# isolated_rs485.net
KiCad netlist of a schematic drawn in Altium Designer
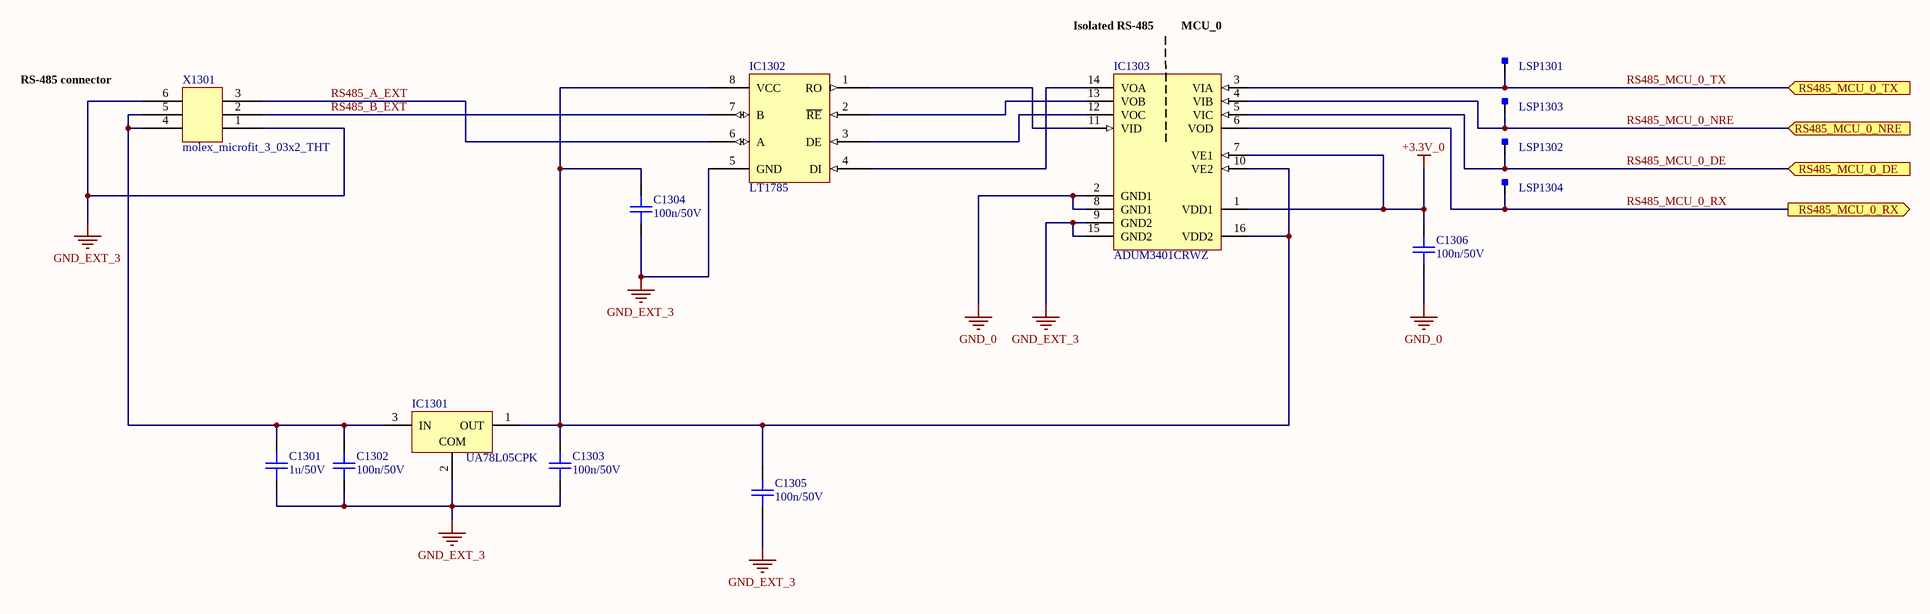
[diagram p0: isolated_rs485.SchDoc]

(export (version "E")
  (design (tool "Eeschema 10.0.6"))
  (components
    (comp (ref "C1301")
      (value "1u/50V")
      (footprint "CAPC1608X08N")
      (description "MLCC")
      (fields (field (name "PART NUMBER") "gen_C_ceramic_1u_50V_X7R_0603") (field (name "TOLERANCE") "± 10%"))
      (libsource (lib "OE750") (part "C"))
    )
    (comp (ref "C1302")
      (value "100n/50V")
      (footprint "CAPC1608X08N")
      (description "MLCC")
      (fields (field (name "PART NUMBER") "gen_C_ceramic_100n_50V_X7R_0603"))
      (libsource (lib "OE750") (part "C"))
    )
    (comp (ref "C1303")
      (value "100n/50V")
      (footprint "CAPC1608X08N")
      (description "MLCC")
      (fields (field (name "PART NUMBER") "gen_C_ceramic_100n_50V_X7R_0603"))
      (libsource (lib "OE750") (part "C"))
    )
    (comp (ref "C1304")
      (value "100n/50V")
      (footprint "CAPC1608X08N")
      (description "MLCC")
      (fields (field (name "PART NUMBER") "gen_C_ceramic_100n_50V_X7R_0603"))
      (libsource (lib "OE750") (part "C"))
    )
    (comp (ref "C1305")
      (value "100n/50V")
      (footprint "CAPC1608X08N")
      (description "MLCC")
      (fields (field (name "PART NUMBER") "gen_C_ceramic_100n_50V_X7R_0603"))
      (libsource (lib "OE750") (part "C"))
    )
    (comp (ref "C1306")
      (value "100n/50V")
      (footprint "CAPC1608X08N")
      (description "MLCC")
      (fields (field (name "PART NUMBER") "gen_C_ceramic_100n_50V_X7R_0603"))
      (libsource (lib "OE750") (part "C"))
    )
    (comp (ref "IC1301")
      (value "UA78L05CPK")
      (footprint "PK0003A_L")
      (fields (field (name "MANUFACTURER") "TexasInstruments"))
      (libsource (lib "Altium Content Vault") (part "TI-UA78L05-PK-3"))
    )
    (comp (ref "IC1302")
      (value "LT1785")
      (footprint "SOIC127P600X175-8N")
      (description "Transceiver RS422/RS485, Fault Protected, 4.75V-5.25V supply, SOIC-8")
      (fields (field (name "PART NUMBER") "LT1785CS8#PBF") (field (name "MANUFACTURER") "Linear Technology"))
      (libsource (lib "OE750") (part "LT1785"))
    )
    (comp (ref "IC1303")
      (value "ADUM3401CRWZ")
      (footprint "ADI-RW-16_N")
      (fields (field (name "MANUFACTURER") "Analog Devices"))
      (libsource (lib "Altium Content Vault") (part "ADI-ADUMX4X1-16"))
    )
    (comp (ref "LSP1301")
      (value "Testpoint_Square")
      (footprint "Testpoint_S1")
      (description "Testpoint, square")
      (libsource (lib "OE750") (part "Testpoint_Square"))
    )
    (comp (ref "LSP1302")
      (value "Testpoint_Square")
      (footprint "Testpoint_S1")
      (description "Testpoint, square")
      (libsource (lib "OE750") (part "Testpoint_Square"))
    )
    (comp (ref "LSP1303")
      (value "Testpoint_Square")
      (footprint "Testpoint_S1")
      (description "Testpoint, square")
      (libsource (lib "OE750") (part "Testpoint_Square"))
    )
    (comp (ref "LSP1304")
      (value "Testpoint_Square")
      (footprint "Testpoint_S1")
      (description "Testpoint, square")
      (libsource (lib "OE750") (part "Testpoint_Square"))
    )
    (comp (ref "X1301")
      (value "molex_microfit_3_03x2_THT")
      (footprint "43045-0621")
      (fields (field (name "MANUFACTURER") "Molex"))
      (libsource (lib "OE750") (part "X3x2"))
    )
  )
  (nets
    (net (code "1") (name "+3.3V_0") (class "Default")
      (node (ref "C1306") (pin "1") (pinfunction "1_1") (pintype "passive"))
      (node (ref "IC1303") (pin "1") (pinfunction "VDD1_1") (pintype "power_in"))
      (node (ref "IC1303") (pin "7") (pinfunction "VE1_7") (pintype "input"))
    )
    (net (code "2") (name "/RS485_A_EXT") (class "Default")
      (node (ref "IC1302") (pin "6") (pinfunction "A_6") (pintype "bidirectional"))
      (node (ref "X1301") (pin "3") (pintype "passive"))
    )
    (net (code "3") (name "/RS485_B_EXT") (class "Default")
      (node (ref "IC1302") (pin "7") (pinfunction "B_7") (pintype "bidirectional"))
      (node (ref "X1301") (pin "2") (pintype "passive"))
    )
    (net (code "4") (name "/RS485_MCU_0_DE") (class "Default")
      (node (ref "IC1303") (pin "5") (pinfunction "VIC_5") (pintype "input"))
      (node (ref "LSP1302") (pin "1") (pinfunction "1_1") (pintype "passive"))
    )
    (net (code "5") (name "/RS485_MCU_0_NRE") (class "Default")
      (node (ref "IC1303") (pin "4") (pinfunction "VIB_4") (pintype "input"))
      (node (ref "LSP1303") (pin "1") (pinfunction "1_1") (pintype "passive"))
    )
    (net (code "6") (name "/RS485_MCU_0_RX") (class "Default")
      (node (ref "IC1303") (pin "6") (pinfunction "VOD_6") (pintype "tri_state"))
      (node (ref "LSP1304") (pin "1") (pinfunction "1_1") (pintype "passive"))
    )
    (net (code "7") (name "/RS485_MCU_0_TX") (class "Default")
      (node (ref "IC1303") (pin "3") (pinfunction "VIA_3") (pintype "input"))
      (node (ref "LSP1301") (pin "1") (pinfunction "1_1") (pintype "passive"))
    )
    (net (code "8") (name "GND_0") (class "Default")
      (node (ref "C1306") (pin "2") (pinfunction "2_2") (pintype "passive"))
      (node (ref "IC1303") (pin "2") (pinfunction "GND1_2") (pintype "power_in"))
      (node (ref "IC1303") (pin "8") (pinfunction "GND1_8") (pintype "power_in"))
    )
    (net (code "9") (name "GND_EXT_3") (class "Default")
      (node (ref "C1301") (pin "2") (pinfunction "2_2") (pintype "passive"))
      (node (ref "C1302") (pin "2") (pinfunction "2_2") (pintype "passive"))
      (node (ref "C1303") (pin "2") (pinfunction "2_2") (pintype "passive"))
      (node (ref "C1304") (pin "2") (pinfunction "2_2") (pintype "passive"))
      (node (ref "C1305") (pin "2") (pinfunction "2_2") (pintype "passive"))
      (node (ref "IC1301") (pin "2") (pinfunction "COM_2") (pintype "power_in"))
      (node (ref "IC1302") (pin "5") (pinfunction "GND_5") (pintype "power_in"))
      (node (ref "IC1303") (pin "15") (pinfunction "GND2_15") (pintype "power_in"))
      (node (ref "IC1303") (pin "9") (pinfunction "GND2_9") (pintype "power_in"))
      (node (ref "X1301") (pin "1") (pintype "passive"))
      (node (ref "X1301") (pin "6") (pintype "passive"))
    )
    (net (code "10") (name "Net-(IC1301-IN)") (class "Default")
      (node (ref "C1301") (pin "1") (pinfunction "1_1") (pintype "passive"))
      (node (ref "C1302") (pin "1") (pinfunction "1_1") (pintype "passive"))
      (node (ref "IC1301") (pin "3") (pinfunction "IN_3") (pintype "power_in"))
      (node (ref "X1301") (pin "4") (pintype "passive"))
      (node (ref "X1301") (pin "5") (pintype "passive"))
    )
    (net (code "11") (name "Net-(IC1301-OUT)") (class "Default")
      (node (ref "C1303") (pin "1") (pinfunction "1_1") (pintype "passive"))
      (node (ref "C1304") (pin "1") (pinfunction "1_1") (pintype "passive"))
      (node (ref "C1305") (pin "1") (pinfunction "1_1") (pintype "passive"))
      (node (ref "IC1301") (pin "1") (pinfunction "OUT_1") (pintype "power_in"))
      (node (ref "IC1302") (pin "8") (pinfunction "VCC_8") (pintype "power_in"))
      (node (ref "IC1303") (pin "10") (pinfunction "VE2_10") (pintype "input"))
      (node (ref "IC1303") (pin "16") (pinfunction "VDD2_16") (pintype "power_in"))
    )
    (net (code "12") (name "Net-(IC1302-DE)") (class "Default")
      (node (ref "IC1302") (pin "3") (pinfunction "DE_3") (pintype "input"))
      (node (ref "IC1303") (pin "12") (pinfunction "VOC_12") (pintype "tri_state"))
    )
    (net (code "13") (name "Net-(IC1302-DI)") (class "Default")
      (node (ref "IC1302") (pin "4") (pinfunction "DI_4") (pintype "input"))
      (node (ref "IC1303") (pin "14") (pinfunction "VOA_14") (pintype "tri_state"))
    )
    (net (code "14") (name "Net-(IC1302-RO)") (class "Default")
      (node (ref "IC1302") (pin "1") (pinfunction "RO_1") (pintype "output"))
      (node (ref "IC1303") (pin "11") (pinfunction "VID_11") (pintype "input"))
    )
    (net (code "15") (name "Net-(IC1302-~{RE})") (class "Default")
      (node (ref "IC1302") (pin "2") (pinfunction "~{RE}_2") (pintype "input"))
      (node (ref "IC1303") (pin "13") (pinfunction "VOB_13") (pintype "tri_state"))
    )
  )
)
